# CN-Cape001.net
KiCad netlist of a schematic drawn in EAGLE
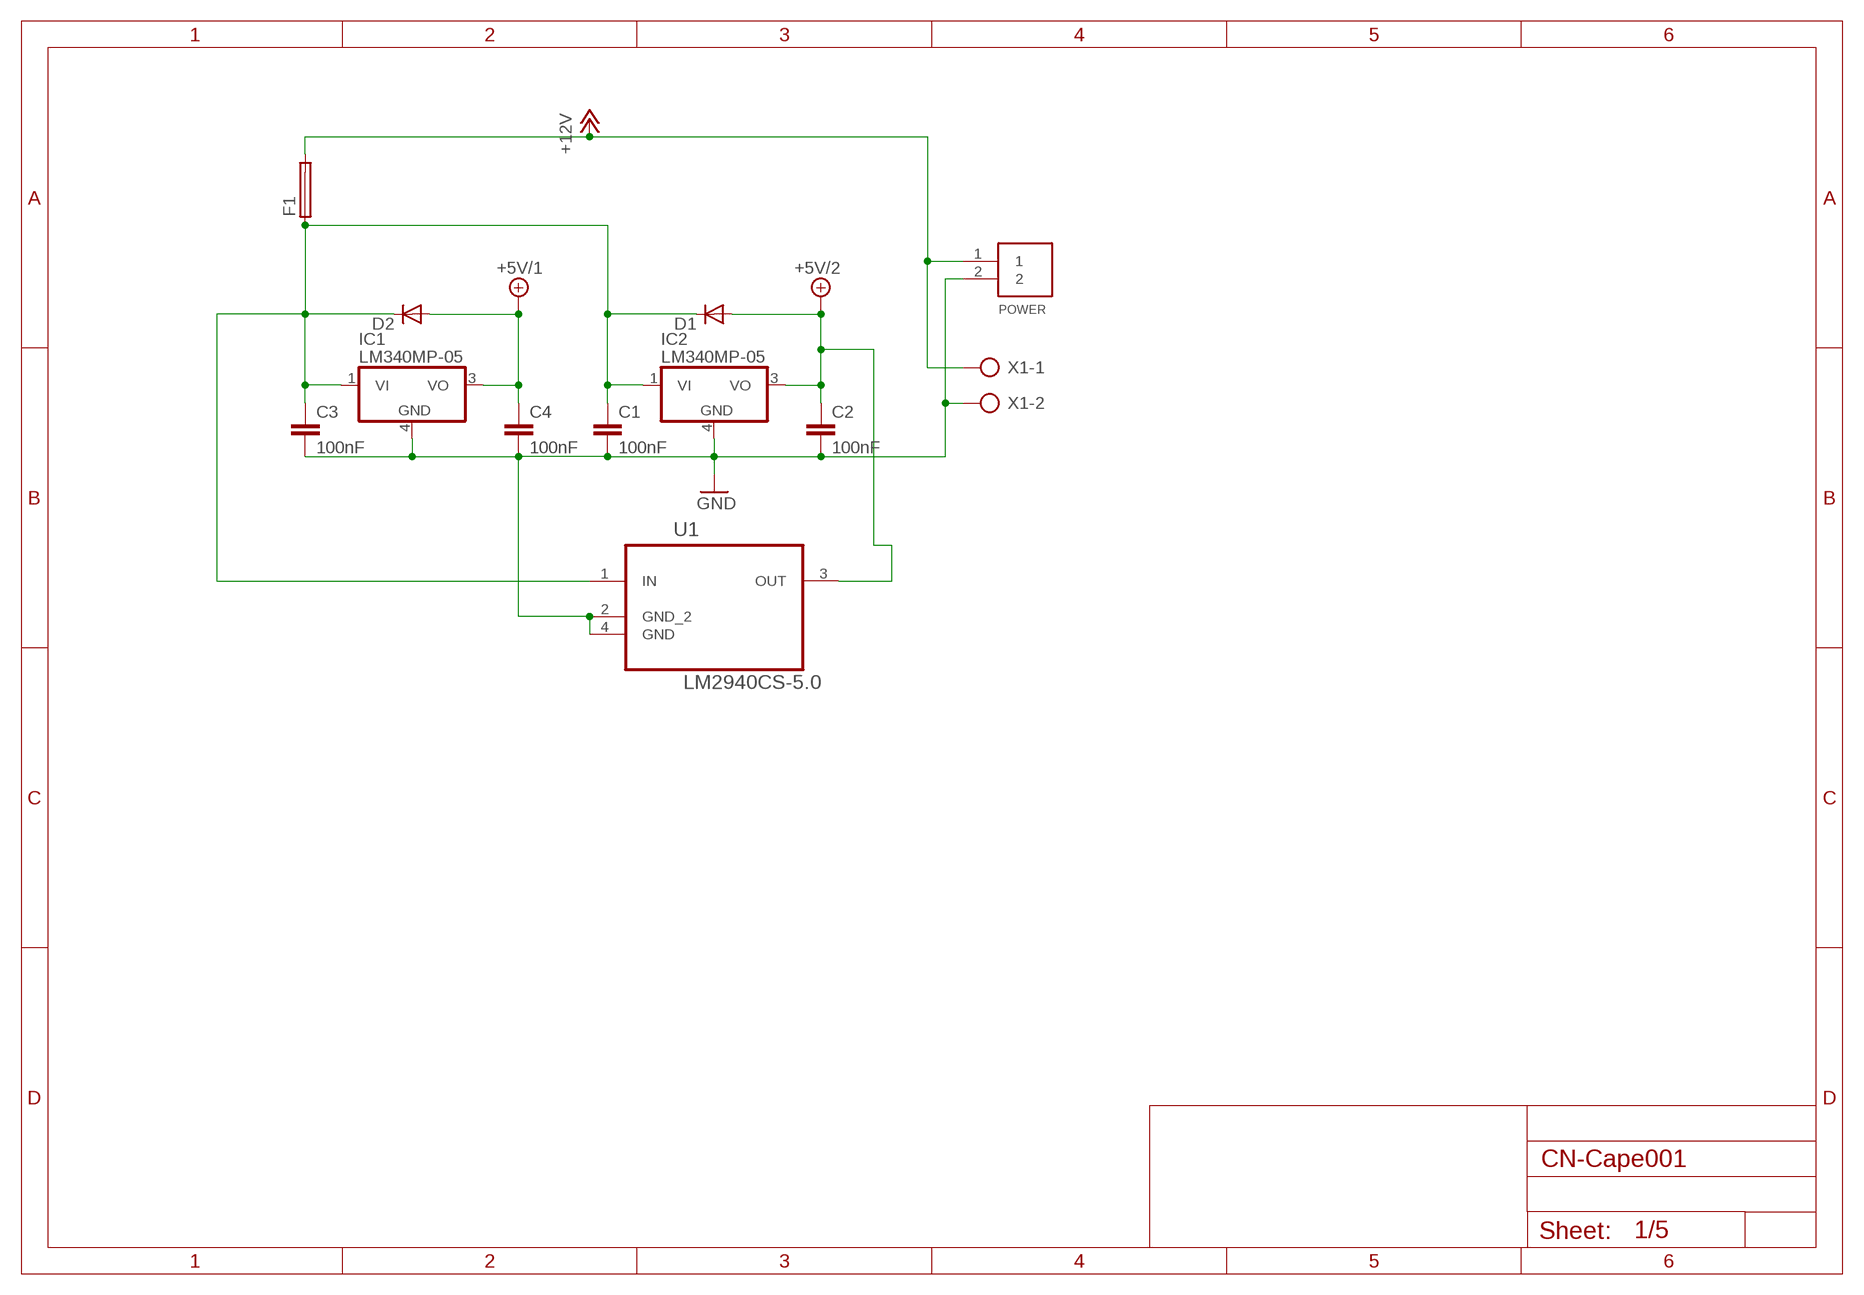
[diagram p0: schematic, sheet 1]
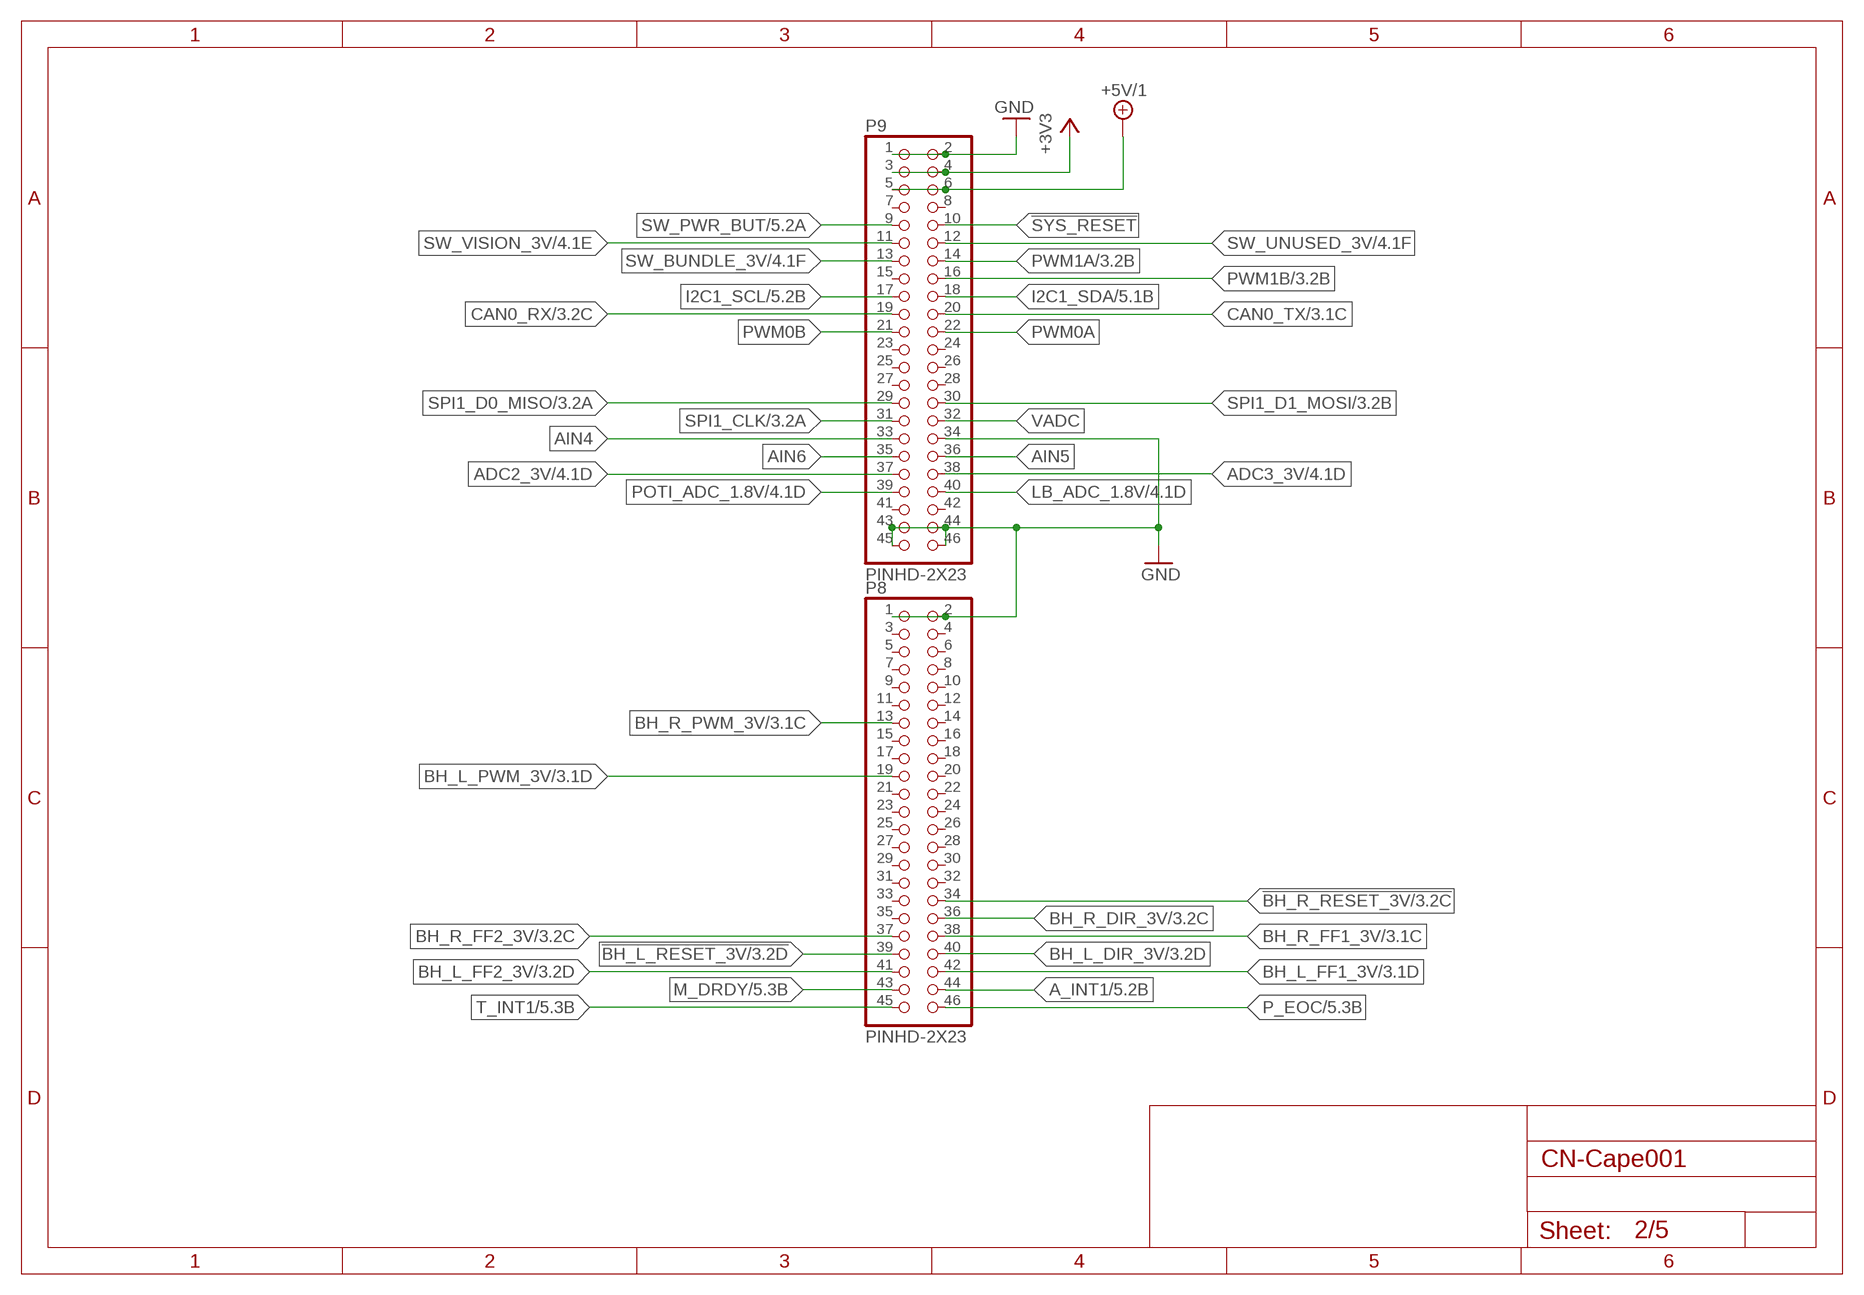
[diagram p1: schematic, sheet 2]
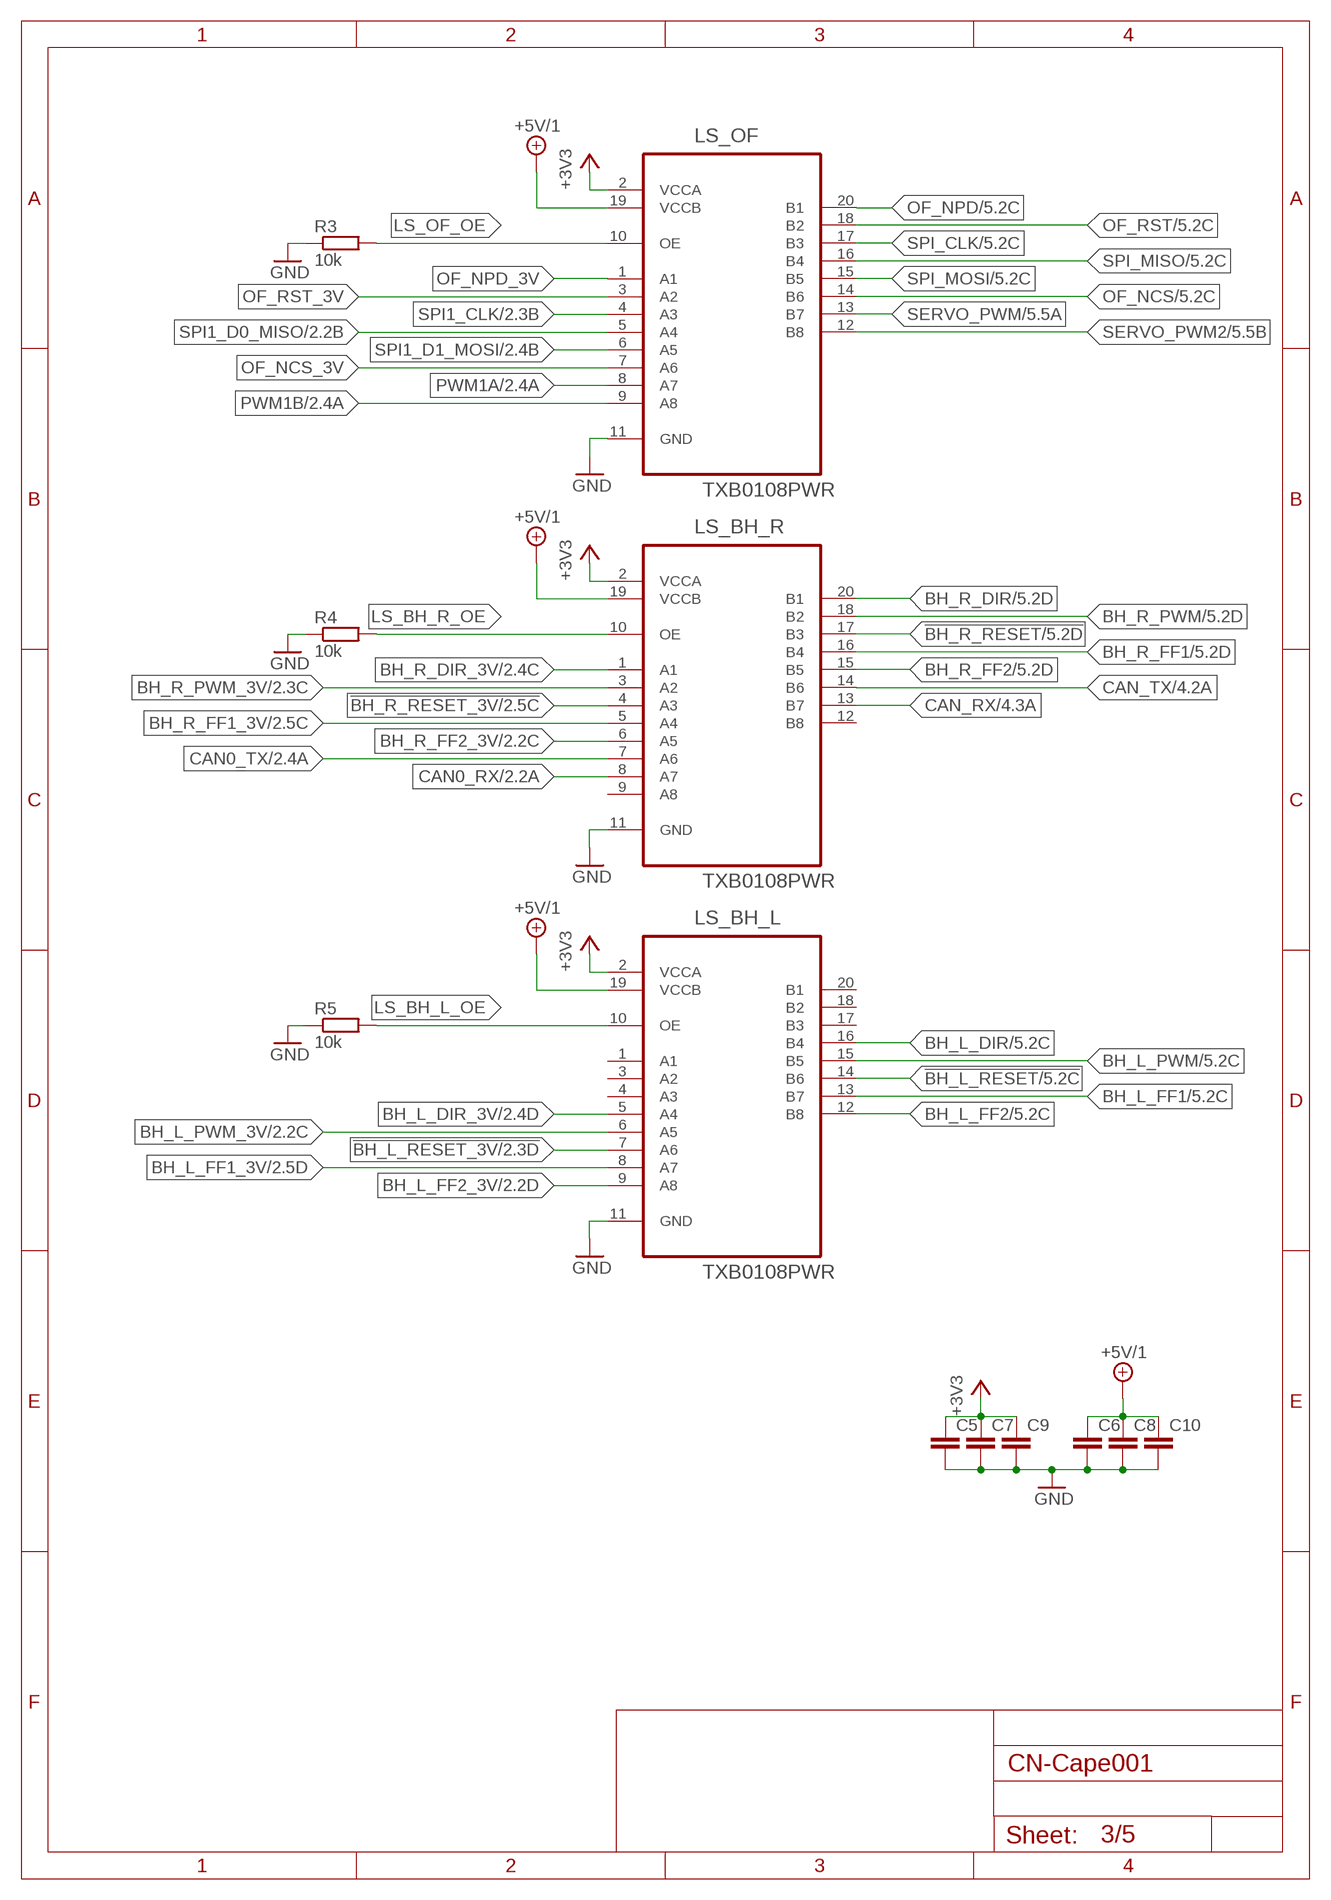
[diagram p2: schematic, sheet 3]
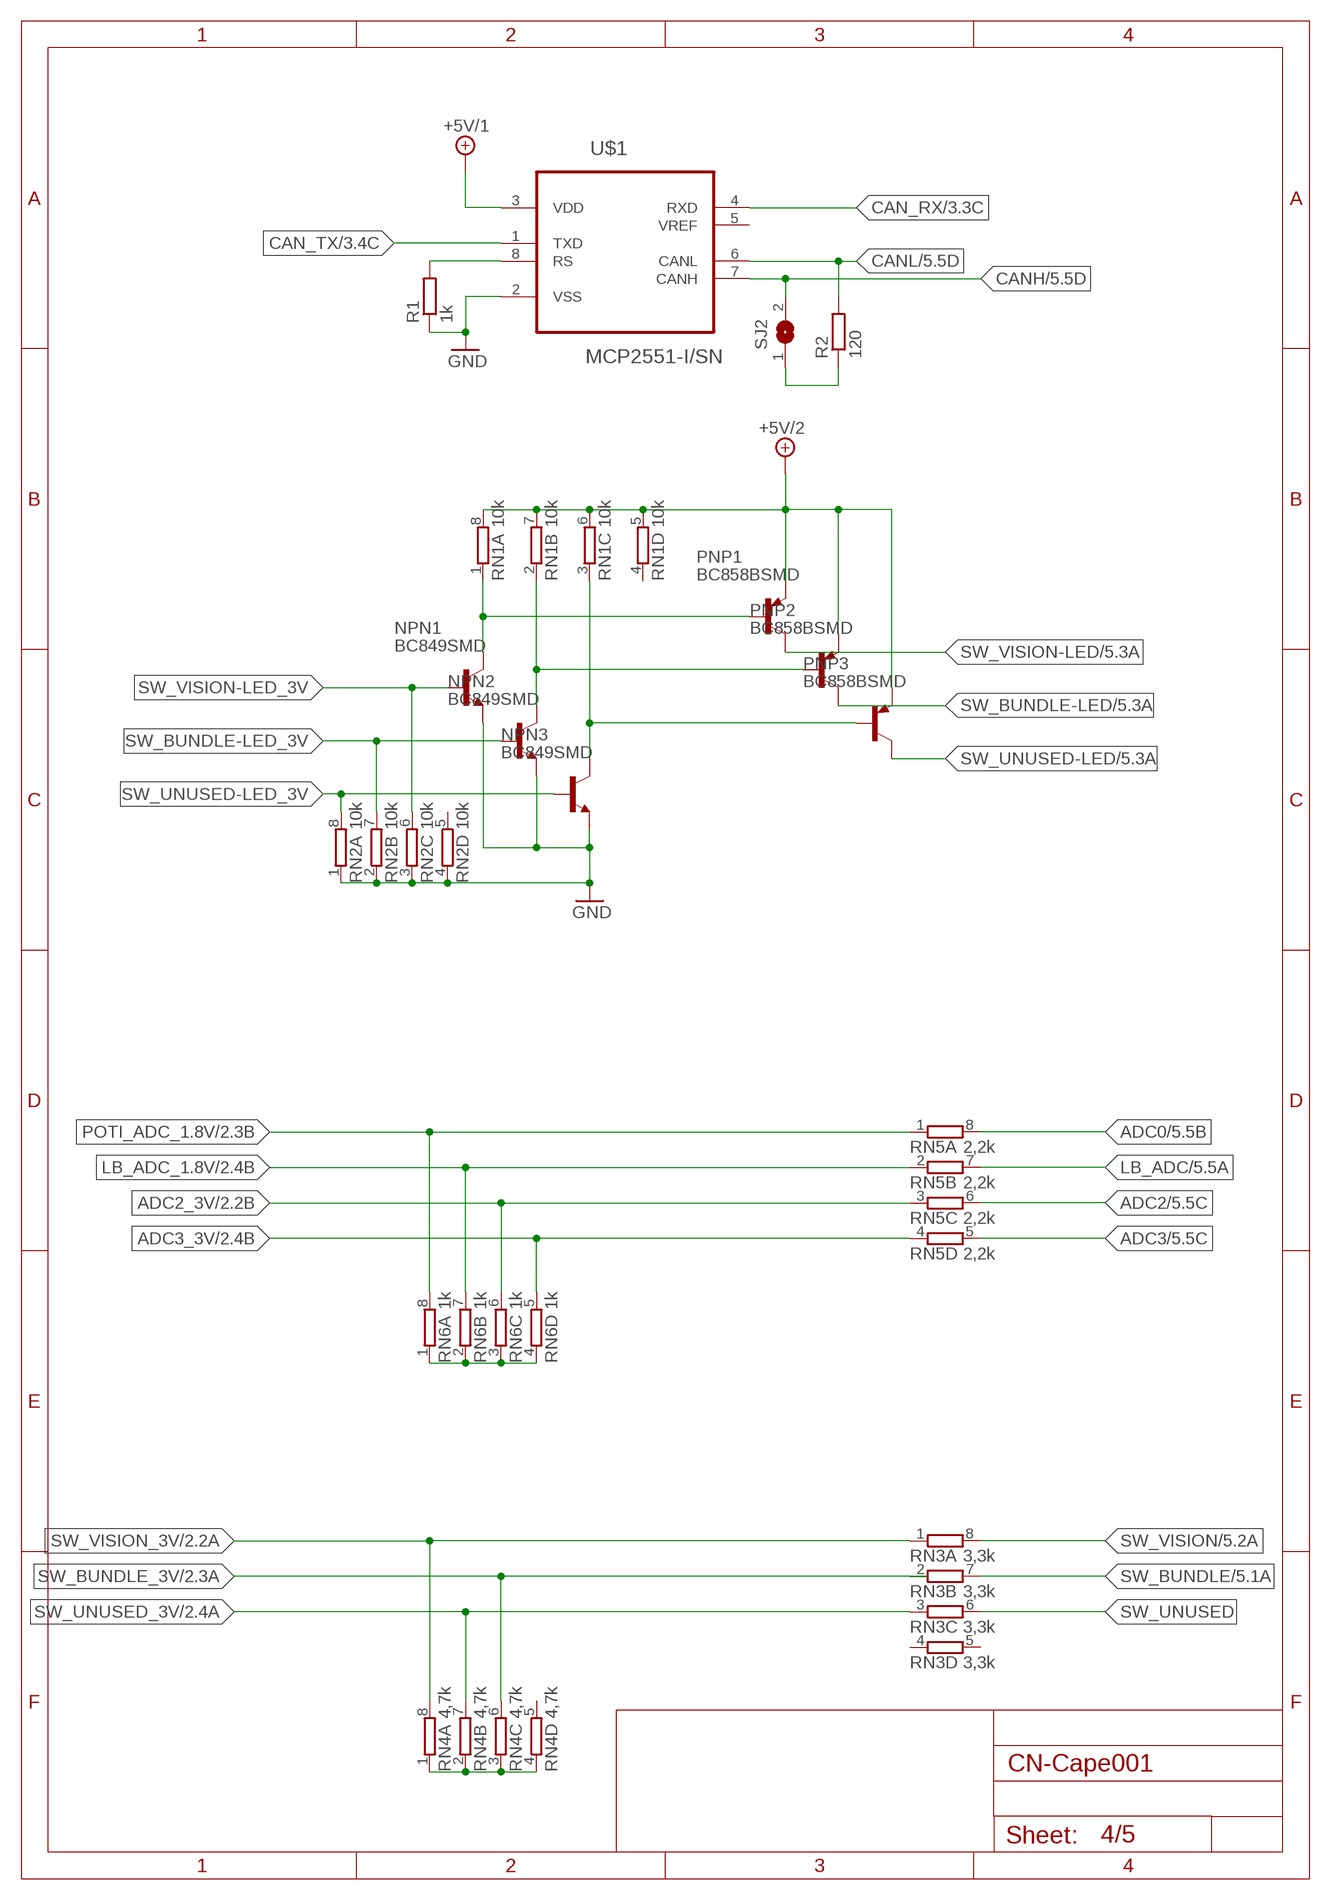
[diagram p3: schematic, sheet 4]
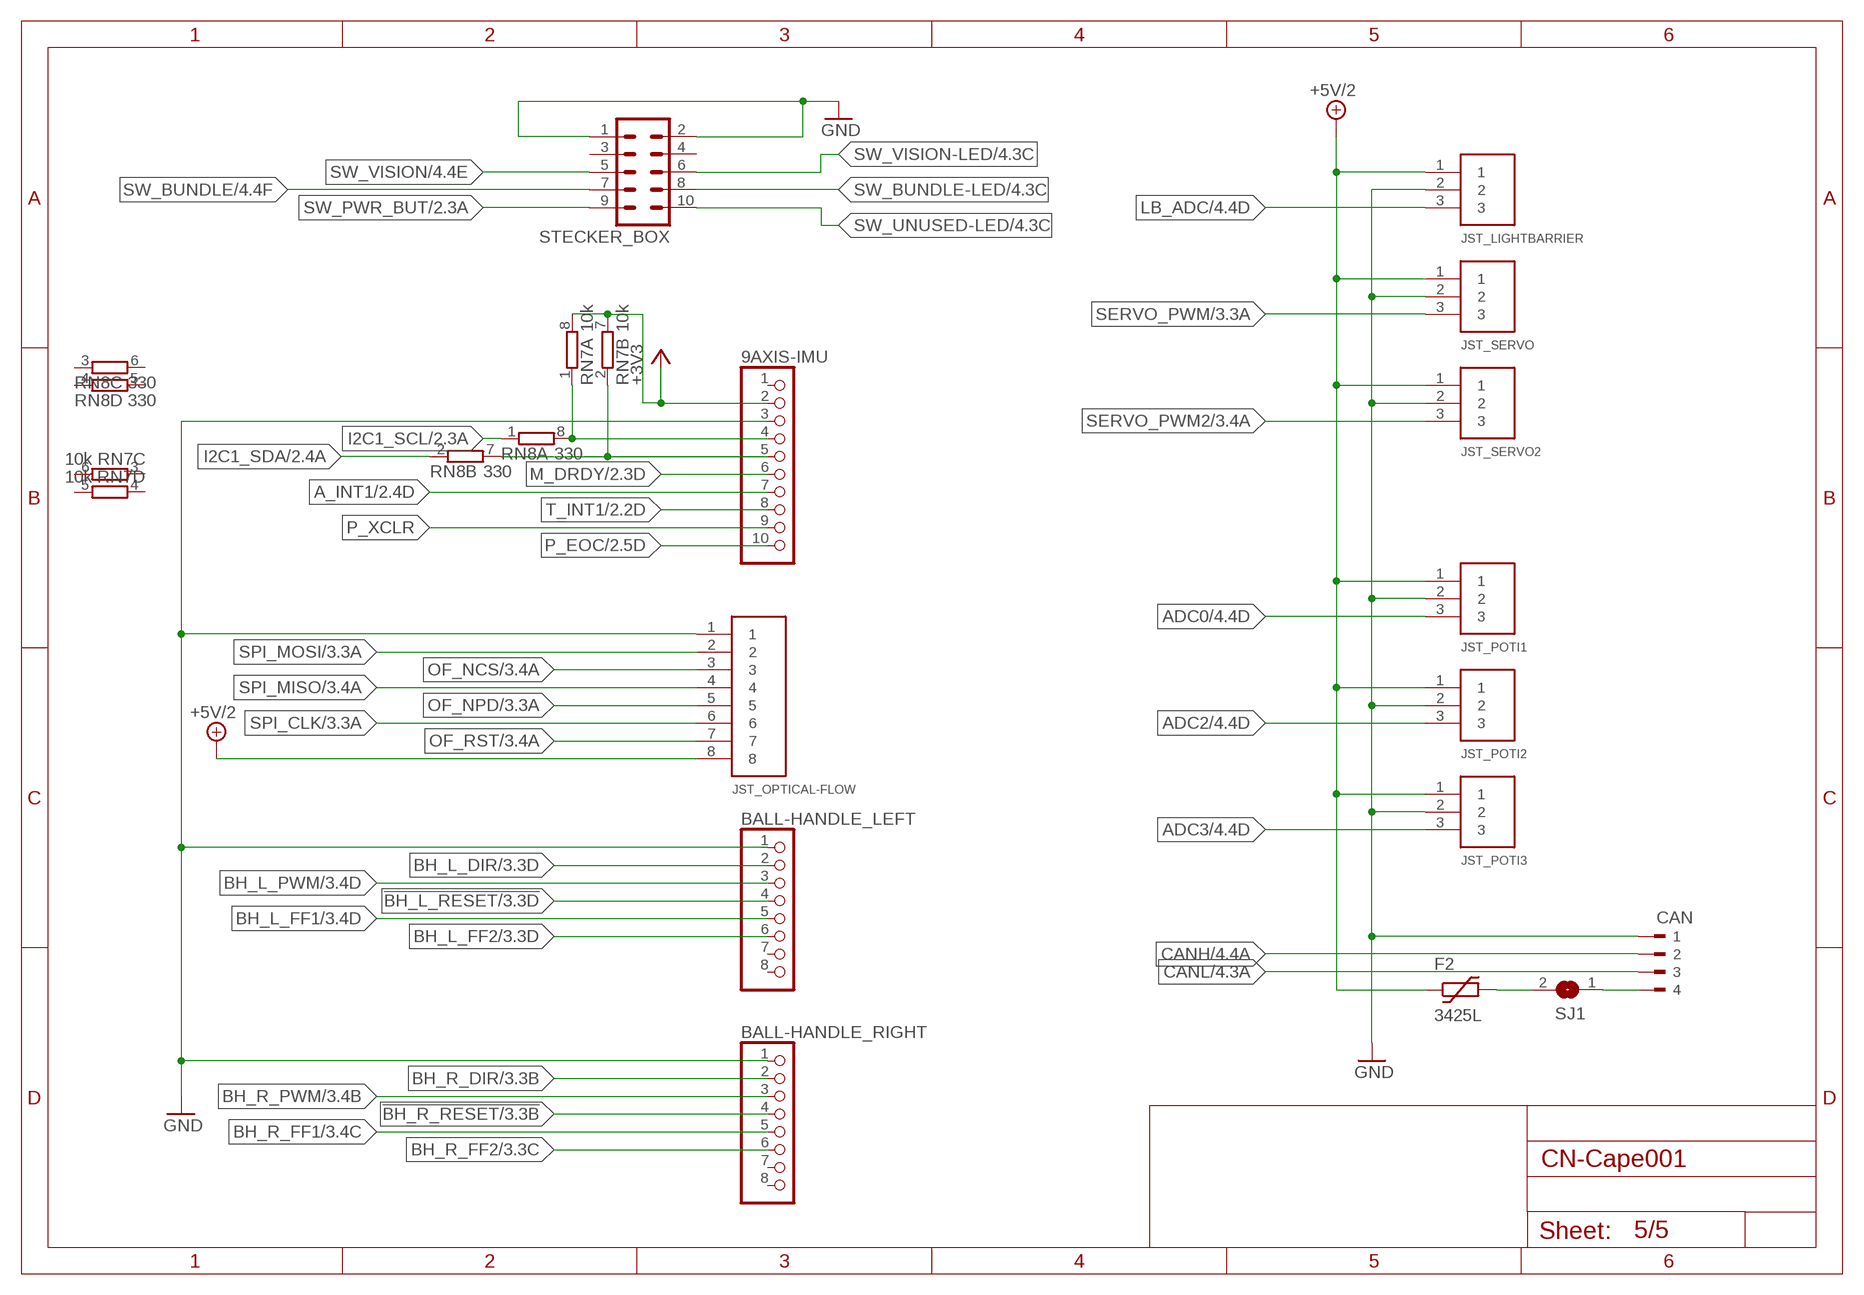
[diagram p4: schematic, sheet 5]

(export (version "E")
  (design (tool "Eeschema 10.0.6"))
  (components
    (comp (ref "C1")
      (value "100nF")
      (footprint "eagle-import:C0805")
      (libsource (lib "eagle-import") (part "C-EUC0805"))
    )
    (comp (ref "C2")
      (value "100nF")
      (footprint "eagle-import:C0805")
      (libsource (lib "eagle-import") (part "C-EUC0805"))
    )
    (comp (ref "C3")
      (value "100nF")
      (footprint "eagle-import:C0805")
      (libsource (lib "eagle-import") (part "C-EUC0805"))
    )
    (comp (ref "C4")
      (value "100nF")
      (footprint "eagle-import:C0805")
      (libsource (lib "eagle-import") (part "C-EUC0805"))
    )
    (comp (ref "D1")
      (value "DIODE-SOD123")
      (footprint "eagle-import:SOD123")
      (libsource (lib "eagle-import") (part "DIODE-SOD123"))
    )
    (comp (ref "D2")
      (value "DIODE-SOD123")
      (footprint "eagle-import:SOD123")
      (libsource (lib "eagle-import") (part "DIODE-SOD123"))
    )
    (comp (ref "F1")
      (value "SH22,5")
      (footprint "eagle-import:SH22,5")
      (libsource (lib "eagle-import") (part "SH22,5"))
    )
    (comp (ref "IC1")
      (value "LM340MP-05")
      (footprint "eagle-import:SOT223")
      (libsource (lib "eagle-import") (part "LM340?-MP05"))
    )
    (comp (ref "IC2")
      (value "LM340MP-05")
      (footprint "eagle-import:SOT223")
      (libsource (lib "eagle-import") (part "LM340?-MP05"))
    )
    (comp (ref "POWER")
      (value "S2PIN")
      (footprint "eagle-import:S2B-EH")
      (libsource (lib "eagle-import") (part "S2PIN"))
    )
    (comp (ref "U1")
      (value "LM2940CS-5.0")
      (footprint "eagle-import:TO254P1435X464-4N")
      (libsource (lib "eagle-import") (part "LM2940CS-5.0"))
    )
    (comp (ref "X1")
      (value "AK500/2-H")
      (footprint "eagle-import:AK500_2-H")
      (libsource (lib "eagle-import") (part "AK500/2-H"))
    )
    (comp (ref "C5")
      (value "C-EUC0805")
      (footprint "eagle-import:C0805")
      (libsource (lib "eagle-import") (part "C-EUC0805"))
    )
    (comp (ref "C6")
      (value "C-EUC0805")
      (footprint "eagle-import:C0805")
      (libsource (lib "eagle-import") (part "C-EUC0805"))
    )
    (comp (ref "C7")
      (value "C-EUC0805")
      (footprint "eagle-import:C0805")
      (libsource (lib "eagle-import") (part "C-EUC0805"))
    )
    (comp (ref "C8")
      (value "C-EUC0805")
      (footprint "eagle-import:C0805")
      (libsource (lib "eagle-import") (part "C-EUC0805"))
    )
    (comp (ref "C9")
      (value "C-EUC0805")
      (footprint "eagle-import:C0805")
      (libsource (lib "eagle-import") (part "C-EUC0805"))
    )
    (comp (ref "C10")
      (value "C-EUC0805")
      (footprint "eagle-import:C0805")
      (libsource (lib "eagle-import") (part "C-EUC0805"))
    )
    (comp (ref "LS_BH_L")
      (value "TXB0108PWR")
      (footprint "eagle-import:SOP65P640X120-20N")
      (libsource (lib "eagle-import") (part "TXB0108PWR"))
    )
    (comp (ref "LS_BH_R")
      (value "TXB0108PWR")
      (footprint "eagle-import:SOP65P640X120-20N")
      (libsource (lib "eagle-import") (part "TXB0108PWR"))
    )
    (comp (ref "LS_OF")
      (value "TXB0108PWR")
      (footprint "eagle-import:SOP65P640X120-20N")
      (libsource (lib "eagle-import") (part "TXB0108PWR"))
    )
    (comp (ref "R3")
      (value "10k")
      (footprint "eagle-import:R0603")
      (libsource (lib "eagle-import") (part "R-EU_R0603"))
    )
    (comp (ref "R4")
      (value "10k")
      (footprint "eagle-import:R0603")
      (libsource (lib "eagle-import") (part "R-EU_R0603"))
    )
    (comp (ref "R5")
      (value "10k")
      (footprint "eagle-import:R0603")
      (libsource (lib "eagle-import") (part "R-EU_R0603"))
    )
    (comp (ref "NPN1")
      (value "BC849SMD")
      (footprint "eagle-import:SOT23-BEC")
      (libsource (lib "eagle-import") (part "BC849SMD"))
    )
    (comp (ref "NPN2")
      (value "BC849SMD")
      (footprint "eagle-import:SOT23-BEC")
      (libsource (lib "eagle-import") (part "BC849SMD"))
    )
    (comp (ref "NPN3")
      (value "BC849SMD")
      (footprint "eagle-import:SOT23-BEC")
      (libsource (lib "eagle-import") (part "BC849SMD"))
    )
    (comp (ref "PNP1")
      (value "BC858BSMD")
      (footprint "eagle-import:SOT23-BEC")
      (libsource (lib "eagle-import") (part "BC858SMDB"))
    )
    (comp (ref "PNP2")
      (value "BC858BSMD")
      (footprint "eagle-import:SOT23-BEC")
      (libsource (lib "eagle-import") (part "BC858SMDB"))
    )
    (comp (ref "PNP3")
      (value "BC858BSMD")
      (footprint "eagle-import:SOT23-BEC")
      (libsource (lib "eagle-import") (part "BC858SMDB"))
    )
    (comp (ref "R1")
      (value "1k")
      (footprint "eagle-import:R0603")
      (libsource (lib "eagle-import") (part "R-EU_R0603"))
    )
    (comp (ref "R2")
      (value "120")
      (footprint "eagle-import:R0603")
      (libsource (lib "eagle-import") (part "R-EU_R0603"))
    )
    (comp (ref "RN1")
      (value "10k")
      (footprint "eagle-import:EXBV8V")
      (libsource (lib "eagle-import") (part "4R-NEXBV8V"))
    )
    (comp (ref "RN2")
      (value "10k")
      (footprint "eagle-import:EXBV8V")
      (libsource (lib "eagle-import") (part "4R-NEXBV8V"))
    )
    (comp (ref "RN3")
      (value "3,3k")
      (footprint "eagle-import:EXBV8V")
      (libsource (lib "eagle-import") (part "4R-NEXBV8V"))
    )
    (comp (ref "RN4")
      (value "4,7k")
      (footprint "eagle-import:EXBV8V")
      (libsource (lib "eagle-import") (part "4R-NEXBV8V"))
    )
    (comp (ref "RN5")
      (value "2,2k")
      (footprint "eagle-import:EXBV8V")
      (libsource (lib "eagle-import") (part "4R-NEXBV8V"))
    )
    (comp (ref "RN6")
      (value "1k")
      (footprint "eagle-import:EXBV8V")
      (libsource (lib "eagle-import") (part "4R-NEXBV8V"))
    )
    (comp (ref "SJ2") (value "SJ") (footprint "eagle-import:SJ") (libsource (lib "eagle-import") (part "SJ")))
    (comp (ref "U$1")
      (value "MCP2551-I/SN")
      (footprint "eagle-import:SOIC127P600X175-8N")
      (libsource (lib "eagle-import") (part "MCP2551-I/SN"))
    )
    (comp (ref "9AXIS-IMU")
      (value "PINHD-1X10")
      (footprint "eagle-import:1X10")
      (libsource (lib "eagle-import") (part "PINHD-1X10"))
    )
    (comp (ref "BALL-HANDLE_LEFT")
      (value "PINHD-1X8")
      (footprint "eagle-import:1X08")
      (libsource (lib "eagle-import") (part "PINHD-1X8"))
    )
    (comp (ref "BALL-HANDLE_RIGHT")
      (value "PINHD-1X8")
      (footprint "eagle-import:1X08")
      (libsource (lib "eagle-import") (part "PINHD-1X8"))
    )
    (comp (ref "CAN")
      (value "90-4")
      (footprint "eagle-import:90-4")
      (libsource (lib "eagle-import") (part "90-4"))
    )
    (comp (ref "F2")
      (value "3425L")
      (footprint "eagle-import:3425L")
      (libsource (lib "eagle-import") (part "3425L"))
    )
    (comp (ref "JST_LIGHTBARRIER")
      (value "S3PIN")
      (footprint "eagle-import:S3B-EH")
      (libsource (lib "eagle-import") (part "S3PIN"))
    )
    (comp (ref "JST_OPTICAL-FLOW")
      (value "S8PIN")
      (footprint "eagle-import:S8B-EH")
      (libsource (lib "eagle-import") (part "S8PIN"))
    )
    (comp (ref "JST_POTI1")
      (value "3PIN")
      (footprint "eagle-import:B3B-EH")
      (libsource (lib "eagle-import") (part "3PIN"))
    )
    (comp (ref "JST_POTI2")
      (value "3PIN")
      (footprint "eagle-import:B3B-EH")
      (libsource (lib "eagle-import") (part "3PIN"))
    )
    (comp (ref "JST_POTI3")
      (value "3PIN")
      (footprint "eagle-import:B3B-EH")
      (libsource (lib "eagle-import") (part "3PIN"))
    )
    (comp (ref "JST_SERVO")
      (value "S3PIN")
      (footprint "eagle-import:S3B-EH")
      (libsource (lib "eagle-import") (part "S3PIN"))
    )
    (comp (ref "JST_SERVO2")
      (value "3PIN")
      (footprint "eagle-import:B3B-EH")
      (libsource (lib "eagle-import") (part "3PIN"))
    )
    (comp (ref "RN7")
      (value "10k")
      (footprint "eagle-import:EXBV8V")
      (libsource (lib "eagle-import") (part "4R-NEXBV8V"))
    )
    (comp (ref "RN8")
      (value "330")
      (footprint "eagle-import:EXBV8V")
      (libsource (lib "eagle-import") (part "4R-NEXBV8V"))
    )
    (comp (ref "SJ1") (value "SJ") (footprint "eagle-import:SJ") (libsource (lib "eagle-import") (part "SJ")))
    (comp (ref "STECKER_BOX")
      (value "ML10")
      (footprint "eagle-import:ML10")
      (libsource (lib "eagle-import") (part "ML10"))
    )
    (comp (ref "P8")
      (value "PINHD-2X23")
      (footprint "eagle-import:2X23")
      (libsource (lib "eagle-import") (part "PINHD-2X23"))
    )
    (comp (ref "P9")
      (value "PINHD-2X23")
      (footprint "eagle-import:2X23")
      (libsource (lib "eagle-import") (part "PINHD-2X23"))
    )
  )
  (nets
    (net (code "1") (name "+3V3") (class "Default")
      (node (ref "9AXIS-IMU") (pin "2") (pinfunction "2_2") (pintype "passive"))
      (node (ref "C5") (pin "1") (pinfunction "1_1") (pintype "passive"))
      (node (ref "C7") (pin "1") (pinfunction "1_1") (pintype "passive"))
      (node (ref "C9") (pin "1") (pinfunction "1_1") (pintype "passive"))
      (node (ref "LS_BH_L") (pin "2") (pinfunction "VCCA_2") (pintype "power_in"))
      (node (ref "LS_BH_R") (pin "2") (pinfunction "VCCA_2") (pintype "power_in"))
      (node (ref "LS_OF") (pin "2") (pinfunction "VCCA_2") (pintype "power_in"))
      (node (ref "P9") (pin "3") (pinfunction "3_3") (pintype "passive"))
      (node (ref "P9") (pin "4") (pinfunction "4_4") (pintype "passive"))
      (node (ref "RN7") (pin "7") (pinfunction "2_7") (pintype "passive"))
      (node (ref "RN7") (pin "8") (pinfunction "2_8") (pintype "passive"))
    )
    (net (code "2") (name "+5V{slash}1") (class "Default")
      (node (ref "C10") (pin "1") (pinfunction "1_1") (pintype "passive"))
      (node (ref "C4") (pin "1") (pinfunction "1_1") (pintype "passive"))
      (node (ref "C6") (pin "1") (pinfunction "1_1") (pintype "passive"))
      (node (ref "C8") (pin "1") (pinfunction "1_1") (pintype "passive"))
      (node (ref "D2") (pin "A") (pinfunction "A_A") (pintype "passive"))
      (node (ref "IC1") (pin "3") (pinfunction "VO_3") (pintype "passive"))
      (node (ref "LS_BH_L") (pin "19") (pinfunction "VCCB_19") (pintype "power_in"))
      (node (ref "LS_BH_R") (pin "19") (pinfunction "VCCB_19") (pintype "power_in"))
      (node (ref "LS_OF") (pin "19") (pinfunction "VCCB_19") (pintype "power_in"))
      (node (ref "P9") (pin "5") (pinfunction "5_5") (pintype "passive"))
      (node (ref "P9") (pin "6") (pinfunction "6_6") (pintype "passive"))
      (node (ref "U$1") (pin "3") (pinfunction "VDD_3") (pintype "power_in"))
    )
    (net (code "3") (name "+5V{slash}2") (class "Default")
      (node (ref "C2") (pin "1") (pinfunction "1_1") (pintype "passive"))
      (node (ref "D1") (pin "A") (pinfunction "A_A") (pintype "passive"))
      (node (ref "F2") (pin "P$1") (pinfunction "1_P$1") (pintype "passive"))
      (node (ref "IC2") (pin "3") (pinfunction "VO_3") (pintype "passive"))
      (node (ref "JST_LIGHTBARRIER") (pin "1") (pinfunction "1_1") (pintype "bidirectional"))
      (node (ref "JST_OPTICAL-FLOW") (pin "8") (pinfunction "8_8") (pintype "bidirectional"))
      (node (ref "JST_POTI1") (pin "1") (pinfunction "1_1") (pintype "bidirectional"))
      (node (ref "JST_POTI2") (pin "1") (pinfunction "1_1") (pintype "bidirectional"))
      (node (ref "JST_POTI3") (pin "1") (pinfunction "1_1") (pintype "bidirectional"))
      (node (ref "JST_SERVO") (pin "1") (pinfunction "1_1") (pintype "bidirectional"))
      (node (ref "JST_SERVO2") (pin "1") (pinfunction "1_1") (pintype "bidirectional"))
      (node (ref "PNP1") (pin "E") (pinfunction "E_E") (pintype "passive"))
      (node (ref "PNP2") (pin "E") (pinfunction "E_E") (pintype "passive"))
      (node (ref "PNP3") (pin "E") (pinfunction "E_E") (pintype "passive"))
      (node (ref "RN1") (pin "5") (pinfunction "2_5") (pintype "passive"))
      (node (ref "RN1") (pin "6") (pinfunction "2_6") (pintype "passive"))
      (node (ref "RN1") (pin "7") (pinfunction "2_7") (pintype "passive"))
      (node (ref "RN1") (pin "8") (pinfunction "2_8") (pintype "passive"))
      (node (ref "U1") (pin "3") (pinfunction "OUT_3") (pintype "output"))
    )
    (net (code "4") (name "+12V") (class "Default")
      (node (ref "F1") (pin "2") (pinfunction "2_2") (pintype "passive"))
      (node (ref "POWER") (pin "1") (pinfunction "1_1") (pintype "bidirectional"))
      (node (ref "X1") (pin "1") (pinfunction "KL_1") (pintype "passive"))
    )
    (net (code "5") (name "ADC0") (class "Default")
      (node (ref "JST_POTI1") (pin "3") (pinfunction "3_3") (pintype "bidirectional"))
      (node (ref "RN5") (pin "8") (pinfunction "2_8") (pintype "passive"))
    )
    (net (code "6") (name "ADC2") (class "Default")
      (node (ref "JST_POTI2") (pin "3") (pinfunction "3_3") (pintype "bidirectional"))
      (node (ref "RN5") (pin "6") (pinfunction "2_6") (pintype "passive"))
    )
    (net (code "7") (name "ADC2_3V") (class "Default")
      (node (ref "P9") (pin "37") (pinfunction "37_37") (pintype "passive"))
      (node (ref "RN5") (pin "3") (pinfunction "1_3") (pintype "passive"))
      (node (ref "RN6") (pin "6") (pinfunction "2_6") (pintype "passive"))
    )
    (net (code "8") (name "ADC3") (class "Default")
      (node (ref "JST_POTI3") (pin "3") (pinfunction "3_3") (pintype "bidirectional"))
      (node (ref "RN5") (pin "5") (pinfunction "2_5") (pintype "passive"))
    )
    (net (code "9") (name "ADC3_3V") (class "Default")
      (node (ref "P9") (pin "38") (pinfunction "38_38") (pintype "passive"))
      (node (ref "RN5") (pin "4") (pinfunction "1_4") (pintype "passive"))
      (node (ref "RN6") (pin "5") (pinfunction "2_5") (pintype "passive"))
    )
    (net (code "10") (name "AIN4") (class "Default")
      (node (ref "P9") (pin "33") (pinfunction "33_33") (pintype "passive"))
    )
    (net (code "11") (name "AIN5") (class "Default")
      (node (ref "P9") (pin "36") (pinfunction "36_36") (pintype "passive"))
    )
    (net (code "12") (name "AIN6") (class "Default")
      (node (ref "P9") (pin "35") (pinfunction "35_35") (pintype "passive"))
    )
    (net (code "13") (name "A_INT1") (class "Default")
      (node (ref "9AXIS-IMU") (pin "7") (pinfunction "7_7") (pintype "passive"))
      (node (ref "P8") (pin "44") (pinfunction "44_44") (pintype "passive"))
    )
    (net (code "14") (name "BH_L_DIR") (class "Default")
      (node (ref "BALL-HANDLE_LEFT") (pin "2") (pinfunction "2_2") (pintype "passive"))
      (node (ref "LS_BH_L") (pin "16") (pinfunction "B4_16") (pintype "bidirectional"))
    )
    (net (code "15") (name "BH_L_DIR_3V") (class "Default")
      (node (ref "LS_BH_L") (pin "5") (pinfunction "A4_5") (pintype "bidirectional"))
      (node (ref "P8") (pin "40") (pinfunction "40_40") (pintype "passive"))
    )
    (net (code "16") (name "BH_L_FF1") (class "Default")
      (node (ref "BALL-HANDLE_LEFT") (pin "5") (pinfunction "5_5") (pintype "passive"))
      (node (ref "LS_BH_L") (pin "13") (pinfunction "B7_13") (pintype "bidirectional"))
    )
    (net (code "17") (name "BH_L_FF1_3V") (class "Default")
      (node (ref "LS_BH_L") (pin "8") (pinfunction "A7_8") (pintype "bidirectional"))
      (node (ref "P8") (pin "42") (pinfunction "42_42") (pintype "passive"))
    )
    (net (code "18") (name "BH_L_FF2") (class "Default")
      (node (ref "BALL-HANDLE_LEFT") (pin "6") (pinfunction "6_6") (pintype "passive"))
      (node (ref "LS_BH_L") (pin "12") (pinfunction "B8_12") (pintype "bidirectional"))
    )
    (net (code "19") (name "BH_L_FF2_3V") (class "Default")
      (node (ref "LS_BH_L") (pin "9") (pinfunction "A8_9") (pintype "bidirectional"))
      (node (ref "P8") (pin "41") (pinfunction "41_41") (pintype "passive"))
    )
    (net (code "20") (name "BH_L_PWM") (class "Default")
      (node (ref "BALL-HANDLE_LEFT") (pin "3") (pinfunction "3_3") (pintype "passive"))
      (node (ref "LS_BH_L") (pin "15") (pinfunction "B5_15") (pintype "bidirectional"))
    )
    (net (code "21") (name "BH_L_PWM_3V") (class "Default")
      (node (ref "LS_BH_L") (pin "6") (pinfunction "A5_6") (pintype "bidirectional"))
      (node (ref "P8") (pin "19") (pinfunction "19_19") (pintype "passive"))
    )
    (net (code "22") (name "BH_R_DIR") (class "Default")
      (node (ref "BALL-HANDLE_RIGHT") (pin "2") (pinfunction "2_2") (pintype "passive"))
      (node (ref "LS_BH_R") (pin "20") (pinfunction "B1_20") (pintype "bidirectional"))
    )
    (net (code "23") (name "BH_R_DIR_3V") (class "Default")
      (node (ref "LS_BH_R") (pin "1") (pinfunction "A1_1") (pintype "bidirectional"))
      (node (ref "P8") (pin "36") (pinfunction "36_36") (pintype "passive"))
    )
    (net (code "24") (name "BH_R_FF1") (class "Default")
      (node (ref "BALL-HANDLE_RIGHT") (pin "5") (pinfunction "5_5") (pintype "passive"))
      (node (ref "LS_BH_R") (pin "16") (pinfunction "B4_16") (pintype "bidirectional"))
    )
    (net (code "25") (name "BH_R_FF1_3V") (class "Default")
      (node (ref "LS_BH_R") (pin "5") (pinfunction "A4_5") (pintype "bidirectional"))
      (node (ref "P8") (pin "38") (pinfunction "38_38") (pintype "passive"))
    )
    (net (code "26") (name "BH_R_FF2") (class "Default")
      (node (ref "BALL-HANDLE_RIGHT") (pin "6") (pinfunction "6_6") (pintype "passive"))
      (node (ref "LS_BH_R") (pin "15") (pinfunction "B5_15") (pintype "bidirectional"))
    )
    (net (code "27") (name "BH_R_FF2_3V") (class "Default")
      (node (ref "LS_BH_R") (pin "6") (pinfunction "A5_6") (pintype "bidirectional"))
      (node (ref "P8") (pin "37") (pinfunction "37_37") (pintype "passive"))
    )
    (net (code "28") (name "BH_R_PWM") (class "Default")
      (node (ref "BALL-HANDLE_RIGHT") (pin "3") (pinfunction "3_3") (pintype "passive"))
      (node (ref "LS_BH_R") (pin "18") (pinfunction "B2_18") (pintype "bidirectional"))
    )
    (net (code "29") (name "BH_R_PWM_3V") (class "Default")
      (node (ref "LS_BH_R") (pin "3") (pinfunction "A2_3") (pintype "bidirectional"))
      (node (ref "P8") (pin "13") (pinfunction "13_13") (pintype "passive"))
    )
    (net (code "30") (name "CAN0_RX") (class "Default")
      (node (ref "LS_BH_R") (pin "8") (pinfunction "A7_8") (pintype "bidirectional"))
      (node (ref "P9") (pin "19") (pinfunction "19_19") (pintype "passive"))
    )
    (net (code "31") (name "CAN0_TX") (class "Default")
      (node (ref "LS_BH_R") (pin "7") (pinfunction "A6_7") (pintype "bidirectional"))
      (node (ref "P9") (pin "20") (pinfunction "20_20") (pintype "passive"))
    )
    (net (code "32") (name "CANH") (class "Default")
      (node (ref "CAN") (pin "2") (pinfunction "2_2") (pintype "passive"))
      (node (ref "SJ2") (pin "2") (pinfunction "2_2") (pintype "passive"))
      (node (ref "U$1") (pin "7") (pinfunction "CANH_7") (pintype "bidirectional"))
    )
    (net (code "33") (name "CANL") (class "Default")
      (node (ref "CAN") (pin "3") (pinfunction "3_3") (pintype "passive"))
      (node (ref "R2") (pin "2") (pinfunction "2_2") (pintype "passive"))
      (node (ref "U$1") (pin "6") (pinfunction "CANL_6") (pintype "bidirectional"))
    )
    (net (code "34") (name "CAN_RX") (class "Default")
      (node (ref "LS_BH_R") (pin "13") (pinfunction "B7_13") (pintype "bidirectional"))
      (node (ref "U$1") (pin "4") (pinfunction "RXD_4") (pintype "output"))
    )
    (net (code "35") (name "CAN_TX") (class "Default")
      (node (ref "LS_BH_R") (pin "14") (pinfunction "B6_14") (pintype "bidirectional"))
      (node (ref "U$1") (pin "1") (pinfunction "TXD_1") (pintype "input"))
    )
    (net (code "36") (name "GND") (class "Default")
      (node (ref "9AXIS-IMU") (pin "3") (pinfunction "3_3") (pintype "passive"))
      (node (ref "BALL-HANDLE_LEFT") (pin "1") (pinfunction "1_1") (pintype "passive"))
      (node (ref "BALL-HANDLE_RIGHT") (pin "1") (pinfunction "1_1") (pintype "passive"))
      (node (ref "C1") (pin "2") (pinfunction "2_2") (pintype "passive"))
      (node (ref "C10") (pin "2") (pinfunction "2_2") (pintype "passive"))
      (node (ref "C2") (pin "2") (pinfunction "2_2") (pintype "passive"))
      (node (ref "C3") (pin "2") (pinfunction "2_2") (pintype "passive"))
      (node (ref "C4") (pin "2") (pinfunction "2_2") (pintype "passive"))
      (node (ref "C5") (pin "2") (pinfunction "2_2") (pintype "passive"))
      (node (ref "C6") (pin "2") (pinfunction "2_2") (pintype "passive"))
      (node (ref "C7") (pin "2") (pinfunction "2_2") (pintype "passive"))
      (node (ref "C8") (pin "2") (pinfunction "2_2") (pintype "passive"))
      (node (ref "C9") (pin "2") (pinfunction "2_2") (pintype "passive"))
      (node (ref "CAN") (pin "1") (pinfunction "1_1") (pintype "passive"))
      (node (ref "IC1") (pin "4") (pinfunction "GND_4") (pintype "passive"))
      (node (ref "IC2") (pin "4") (pinfunction "GND_4") (pintype "passive"))
      (node (ref "JST_LIGHTBARRIER") (pin "2") (pinfunction "2_2") (pintype "bidirectional"))
      (node (ref "JST_OPTICAL-FLOW") (pin "1") (pinfunction "1_1") (pintype "bidirectional"))
      (node (ref "JST_POTI1") (pin "2") (pinfunction "2_2") (pintype "bidirectional"))
      (node (ref "JST_POTI2") (pin "2") (pinfunction "2_2") (pintype "bidirectional"))
      (node (ref "JST_POTI3") (pin "2") (pinfunction "2_2") (pintype "bidirectional"))
      (node (ref "JST_SERVO") (pin "2") (pinfunction "2_2") (pintype "bidirectional"))
      (node (ref "JST_SERVO2") (pin "2") (pinfunction "2_2") (pintype "bidirectional"))
      (node (ref "LS_BH_L") (pin "11") (pinfunction "GND_11") (pintype "passive"))
      (node (ref "LS_BH_R") (pin "11") (pinfunction "GND_11") (pintype "passive"))
      (node (ref "LS_OF") (pin "11") (pinfunction "GND_11") (pintype "passive"))
      (node (ref "NPN1") (pin "E") (pinfunction "E_E") (pintype "passive"))
      (node (ref "NPN2") (pin "E") (pinfunction "E_E") (pintype "passive"))
      (node (ref "NPN3") (pin "E") (pinfunction "E_E") (pintype "passive"))
      (node (ref "P8") (pin "1") (pinfunction "1_1") (pintype "passive"))
      (node (ref "P8") (pin "2") (pinfunction "2_2") (pintype "passive"))
      (node (ref "P9") (pin "1") (pinfunction "1_1") (pintype "passive"))
      (node (ref "P9") (pin "2") (pinfunction "2_2") (pintype "passive"))
      (node (ref "P9") (pin "34") (pinfunction "34_34") (pintype "passive"))
      (node (ref "P9") (pin "43") (pinfunction "43_43") (pintype "passive"))
      (node (ref "P9") (pin "44") (pinfunction "44_44") (pintype "passive"))
      (node (ref "P9") (pin "45") (pinfunction "45_45") (pintype "passive"))
      (node (ref "P9") (pin "46") (pinfunction "46_46") (pintype "passive"))
      (node (ref "POWER") (pin "2") (pinfunction "2_2") (pintype "bidirectional"))
      (node (ref "R1") (pin "1") (pinfunction "1_1") (pintype "passive"))
      (node (ref "R3") (pin "1") (pinfunction "1_1") (pintype "passive"))
      (node (ref "R4") (pin "1") (pinfunction "1_1") (pintype "passive"))
      (node (ref "R5") (pin "1") (pinfunction "1_1") (pintype "passive"))
      (node (ref "RN2") (pin "1") (pinfunction "1_1") (pintype "passive"))
      (node (ref "RN2") (pin "2") (pinfunction "1_2") (pintype "passive"))
      (node (ref "RN2") (pin "3") (pinfunction "1_3") (pintype "passive"))
      (node (ref "RN2") (pin "4") (pinfunction "1_4") (pintype "passive"))
      (node (ref "STECKER_BOX") (pin "1") (pinfunction "1_1") (pintype "passive"))
      (node (ref "STECKER_BOX") (pin "2") (pinfunction "2_2") (pintype "passive"))
      (node (ref "U$1") (pin "2") (pinfunction "VSS_2") (pintype "passive"))
      (node (ref "U1") (pin "2") (pinfunction "GND_2_2") (pintype "passive"))
      (node (ref "U1") (pin "4") (pinfunction "GND_4") (pintype "passive"))
      (node (ref "X1") (pin "2") (pinfunction "KL_2") (pintype "passive"))
    )
    (net (code "37") (name "I2C1_SCL") (class "Default")
      (node (ref "P9") (pin "17") (pinfunction "17_17") (pintype "passive"))
      (node (ref "RN8") (pin "1") (pinfunction "1_1") (pintype "passive"))
    )
    (net (code "38") (name "I2C1_SDA") (class "Default")
      (node (ref "P9") (pin "18") (pinfunction "18_18") (pintype "passive"))
      (node (ref "RN8") (pin "2") (pinfunction "1_2") (pintype "passive"))
    )
    (net (code "39") (name "LB_ADC") (class "Default")
      (node (ref "JST_LIGHTBARRIER") (pin "3") (pinfunction "3_3") (pintype "bidirectional"))
      (node (ref "RN5") (pin "7") (pinfunction "2_7") (pintype "passive"))
    )
    (net (code "40") (name "LB_ADC_1.8V") (class "Default")
      (node (ref "P9") (pin "40") (pinfunction "40_40") (pintype "passive"))
      (node (ref "RN5") (pin "2") (pinfunction "1_2") (pintype "passive"))
      (node (ref "RN6") (pin "7") (pinfunction "2_7") (pintype "passive"))
    )
    (net (code "41") (name "LS_BH_L_OE") (class "Default")
      (node (ref "LS_BH_L") (pin "10") (pinfunction "OE_10") (pintype "input"))
      (node (ref "R5") (pin "2") (pinfunction "2_2") (pintype "passive"))
    )
    (net (code "42") (name "LS_BH_R_OE") (class "Default")
      (node (ref "LS_BH_R") (pin "10") (pinfunction "OE_10") (pintype "input"))
      (node (ref "R4") (pin "2") (pinfunction "2_2") (pintype "passive"))
    )
    (net (code "43") (name "LS_OF_OE") (class "Default")
      (node (ref "LS_OF") (pin "10") (pinfunction "OE_10") (pintype "input"))
      (node (ref "R3") (pin "2") (pinfunction "2_2") (pintype "passive"))
    )
    (net (code "44") (name "M_DRDY") (class "Default")
      (node (ref "9AXIS-IMU") (pin "6") (pinfunction "6_6") (pintype "passive"))
      (node (ref "P8") (pin "43") (pinfunction "43_43") (pintype "passive"))
    )
    (net (code "45") (name "Net-(CAN-Pad4)") (class "Default")
      (node (ref "CAN") (pin "4") (pinfunction "4_4") (pintype "passive"))
      (node (ref "SJ1") (pin "1") (pinfunction "1_1") (pintype "passive"))
    )
    (net (code "46") (name "Net-(F2-2)") (class "Default")
      (node (ref "F2") (pin "P$2") (pinfunction "2_P$2") (pintype "passive"))
      (node (ref "SJ1") (pin "2") (pinfunction "2_2") (pintype "passive"))
    )
    (net (code "47") (name "Net-(IC1-VI)") (class "Default")
      (node (ref "C1") (pin "1") (pinfunction "1_1") (pintype "passive"))
      (node (ref "C3") (pin "1") (pinfunction "1_1") (pintype "passive"))
      (node (ref "D1") (pin "C") (pinfunction "C_C") (pintype "passive"))
      (node (ref "D2") (pin "C") (pinfunction "C_C") (pintype "passive"))
      (node (ref "F1") (pin "1") (pinfunction "1_1") (pintype "passive"))
      (node (ref "IC1") (pin "1") (pinfunction "VI_1") (pintype "input"))
      (node (ref "IC2") (pin "1") (pinfunction "VI_1") (pintype "input"))
      (node (ref "U1") (pin "1") (pinfunction "IN_1") (pintype "input"))
    )
    (net (code "48") (name "Net-(NPN1-PadC)") (class "Default")
      (node (ref "NPN1") (pin "C") (pinfunction "C_C") (pintype "passive"))
      (node (ref "PNP1") (pin "B") (pinfunction "B_B") (pintype "passive"))
      (node (ref "RN1") (pin "1") (pinfunction "1_1") (pintype "passive"))
    )
    (net (code "49") (name "Net-(R2-Pad1)") (class "Default")
      (node (ref "R2") (pin "1") (pinfunction "1_1") (pintype "passive"))
      (node (ref "SJ2") (pin "1") (pinfunction "1_1") (pintype "passive"))
    )
    (net (code "50") (name "Net-(RN1B-1)") (class "Default")
      (node (ref "NPN2") (pin "C") (pinfunction "C_C") (pintype "passive"))
      (node (ref "PNP2") (pin "B") (pinfunction "B_B") (pintype "passive"))
      (node (ref "RN1") (pin "2") (pinfunction "1_2") (pintype "passive"))
    )
    (net (code "51") (name "Net-(RN1C-1)") (class "Default")
      (node (ref "NPN3") (pin "C") (pinfunction "C_C") (pintype "passive"))
      (node (ref "PNP3") (pin "B") (pinfunction "B_B") (pintype "passive"))
      (node (ref "RN1") (pin "3") (pinfunction "1_3") (pintype "passive"))
    )
    (net (code "52") (name "Net-(RN4B-1)") (class "Default")
      (node (ref "RN4") (pin "1") (pinfunction "1_1") (pintype "passive"))
      (node (ref "RN4") (pin "2") (pinfunction "1_2") (pintype "passive"))
      (node (ref "RN4") (pin "3") (pinfunction "1_3") (pintype "passive"))
      (node (ref "RN4") (pin "4") (pinfunction "1_4") (pintype "passive"))
    )
    (net (code "53") (name "Net-(RN6B-1)") (class "Default")
      (node (ref "RN6") (pin "1") (pinfunction "1_1") (pintype "passive"))
      (node (ref "RN6") (pin "2") (pinfunction "1_2") (pintype "passive"))
      (node (ref "RN6") (pin "3") (pinfunction "1_3") (pintype "passive"))
      (node (ref "RN6") (pin "4") (pinfunction "1_4") (pintype "passive"))
    )
    (net (code "54") (name "Net-(RN7B-1)") (class "Default")
      (node (ref "9AXIS-IMU") (pin "5") (pinfunction "5_5") (pintype "passive"))
      (node (ref "RN7") (pin "2") (pinfunction "1_2") (pintype "passive"))
      (node (ref "RN8") (pin "7") (pinfunction "2_7") (pintype "passive"))
    )
    (net (code "55") (name "Net-(RN8A-2)") (class "Default")
      (node (ref "9AXIS-IMU") (pin "4") (pinfunction "4_4") (pintype "passive"))
      (node (ref "RN7") (pin "1") (pinfunction "1_1") (pintype "passive"))
      (node (ref "RN8") (pin "8") (pinfunction "2_8") (pintype "passive"))
    )
    (net (code "56") (name "Net-(U$1-RS)") (class "Default")
      (node (ref "R1") (pin "2") (pinfunction "2_2") (pintype "passive"))
      (node (ref "U$1") (pin "8") (pinfunction "RS_8") (pintype "input"))
    )
    (net (code "57") (name "OF_NCS") (class "Default")
      (node (ref "JST_OPTICAL-FLOW") (pin "3") (pinfunction "3_3") (pintype "bidirectional"))
      (node (ref "LS_OF") (pin "14") (pinfunction "B6_14") (pintype "bidirectional"))
    )
    (net (code "58") (name "OF_NCS_3V") (class "Default")
      (node (ref "LS_OF") (pin "7") (pinfunction "A6_7") (pintype "bidirectional"))
    )
    (net (code "59") (name "OF_NPD") (class "Default")
      (node (ref "JST_OPTICAL-FLOW") (pin "5") (pinfunction "5_5") (pintype "bidirectional"))
      (node (ref "LS_OF") (pin "20") (pinfunction "B1_20") (pintype "bidirectional"))
    )
    (net (code "60") (name "OF_NPD_3V") (class "Default")
      (node (ref "LS_OF") (pin "1") (pinfunction "A1_1") (pintype "bidirectional"))
    )
    (net (code "61") (name "OF_RST") (class "Default")
      (node (ref "JST_OPTICAL-FLOW") (pin "7") (pinfunction "7_7") (pintype "bidirectional"))
      (node (ref "LS_OF") (pin "18") (pinfunction "B2_18") (pintype "bidirectional"))
    )
    (net (code "62") (name "OF_RST_3V") (class "Default")
      (node (ref "LS_OF") (pin "3") (pinfunction "A2_3") (pintype "bidirectional"))
    )
    (net (code "63") (name "POTI_ADC_1.8V") (class "Default")
      (node (ref "P9") (pin "39") (pinfunction "39_39") (pintype "passive"))
      (node (ref "RN5") (pin "1") (pinfunction "1_1") (pintype "passive"))
      (node (ref "RN6") (pin "8") (pinfunction "2_8") (pintype "passive"))
    )
    (net (code "64") (name "PWM0A") (class "Default")
      (node (ref "P9") (pin "22") (pinfunction "22_22") (pintype "passive"))
    )
    (net (code "65") (name "PWM0B") (class "Default")
      (node (ref "P9") (pin "21") (pinfunction "21_21") (pintype "passive"))
    )
    (net (code "66") (name "PWM1A") (class "Default")
      (node (ref "LS_OF") (pin "8") (pinfunction "A7_8") (pintype "bidirectional"))
      (node (ref "P9") (pin "14") (pinfunction "14_14") (pintype "passive"))
    )
    (net (code "67") (name "PWM1B") (class "Default")
      (node (ref "LS_OF") (pin "9") (pinfunction "A8_9") (pintype "bidirectional"))
      (node (ref "P9") (pin "16") (pinfunction "16_16") (pintype "passive"))
    )
    (net (code "68") (name "P_EOC") (class "Default")
      (node (ref "9AXIS-IMU") (pin "10") (pinfunction "10_10") (pintype "passive"))
      (node (ref "P8") (pin "46") (pinfunction "46_46") (pintype "passive"))
    )
    (net (code "69") (name "P_XCLR") (class "Default")
      (node (ref "9AXIS-IMU") (pin "9") (pinfunction "9_9") (pintype "passive"))
    )
    (net (code "70") (name "SERVO_PWM") (class "Default")
      (node (ref "JST_SERVO") (pin "3") (pinfunction "3_3") (pintype "bidirectional"))
      (node (ref "LS_OF") (pin "13") (pinfunction "B7_13") (pintype "bidirectional"))
    )
    (net (code "71") (name "SERVO_PWM2") (class "Default")
      (node (ref "JST_SERVO2") (pin "3") (pinfunction "3_3") (pintype "bidirectional"))
      (node (ref "LS_OF") (pin "12") (pinfunction "B8_12") (pintype "bidirectional"))
    )
    (net (code "72") (name "SPI1_CLK") (class "Default")
      (node (ref "LS_OF") (pin "4") (pinfunction "A3_4") (pintype "bidirectional"))
      (node (ref "P9") (pin "31") (pinfunction "31_31") (pintype "passive"))
    )
    (net (code "73") (name "SPI1_D0_MISO") (class "Default")
      (node (ref "LS_OF") (pin "5") (pinfunction "A4_5") (pintype "bidirectional"))
      (node (ref "P9") (pin "29") (pinfunction "29_29") (pintype "passive"))
    )
    (net (code "74") (name "SPI1_D1_MOSI") (class "Default")
      (node (ref "LS_OF") (pin "6") (pinfunction "A5_6") (pintype "bidirectional"))
      (node (ref "P9") (pin "30") (pinfunction "30_30") (pintype "passive"))
    )
    (net (code "75") (name "SPI_CLK") (class "Default")
      (node (ref "JST_OPTICAL-FLOW") (pin "6") (pinfunction "6_6") (pintype "bidirectional"))
      (node (ref "LS_OF") (pin "17") (pinfunction "B3_17") (pintype "bidirectional"))
    )
    (net (code "76") (name "SPI_MISO") (class "Default")
      (node (ref "JST_OPTICAL-FLOW") (pin "4") (pinfunction "4_4") (pintype "bidirectional"))
      (node (ref "LS_OF") (pin "16") (pinfunction "B4_16") (pintype "bidirectional"))
    )
    (net (code "77") (name "SPI_MOSI") (class "Default")
      (node (ref "JST_OPTICAL-FLOW") (pin "2") (pinfunction "2_2") (pintype "bidirectional"))
      (node (ref "LS_OF") (pin "15") (pinfunction "B5_15") (pintype "bidirectional"))
    )
    (net (code "78") (name "SW_BUNDLE") (class "Default")
      (node (ref "RN3") (pin "7") (pinfunction "2_7") (pintype "passive"))
      (node (ref "STECKER_BOX") (pin "7") (pinfunction "7_7") (pintype "passive"))
    )
    (net (code "79") (name "SW_BUNDLE-LED") (class "Default")
      (node (ref "PNP2") (pin "C") (pinfunction "C_C") (pintype "passive"))
      (node (ref "STECKER_BOX") (pin "8") (pinfunction "8_8") (pintype "passive"))
    )
    (net (code "80") (name "SW_BUNDLE-LED_3V") (class "Default")
      (node (ref "NPN2") (pin "B") (pinfunction "B_B") (pintype "passive"))
      (node (ref "RN2") (pin "7") (pinfunction "2_7") (pintype "passive"))
    )
    (net (code "81") (name "SW_BUNDLE_3V") (class "Default")
      (node (ref "P9") (pin "13") (pinfunction "13_13") (pintype "passive"))
      (node (ref "RN3") (pin "2") (pinfunction "1_2") (pintype "passive"))
      (node (ref "RN4") (pin "6") (pinfunction "2_6") (pintype "passive"))
    )
    (net (code "82") (name "SW_PWR_BUT") (class "Default")
      (node (ref "P9") (pin "9") (pinfunction "9_9") (pintype "passive"))
      (node (ref "STECKER_BOX") (pin "9") (pinfunction "9_9") (pintype "passive"))
    )
    (net (code "83") (name "SW_UNUSED") (class "Default")
      (node (ref "RN3") (pin "6") (pinfunction "2_6") (pintype "passive"))
    )
    (net (code "84") (name "SW_UNUSED-LED") (class "Default")
      (node (ref "PNP3") (pin "C") (pinfunction "C_C") (pintype "passive"))
      (node (ref "STECKER_BOX") (pin "10") (pinfunction "10_10") (pintype "passive"))
    )
    (net (code "85") (name "SW_UNUSED-LED_3V") (class "Default")
      (node (ref "NPN3") (pin "B") (pinfunction "B_B") (pintype "passive"))
      (node (ref "RN2") (pin "8") (pinfunction "2_8") (pintype "passive"))
    )
    (net (code "86") (name "SW_UNUSED_3V") (class "Default")
      (node (ref "P9") (pin "12") (pinfunction "12_12") (pintype "passive"))
      (node (ref "RN3") (pin "3") (pinfunction "1_3") (pintype "passive"))
      (node (ref "RN4") (pin "7") (pinfunction "2_7") (pintype "passive"))
    )
    (net (code "87") (name "SW_VISION") (class "Default")
      (node (ref "RN3") (pin "8") (pinfunction "2_8") (pintype "passive"))
      (node (ref "STECKER_BOX") (pin "5") (pinfunction "5_5") (pintype "passive"))
    )
    (net (code "88") (name "SW_VISION-LED") (class "Default")
      (node (ref "PNP1") (pin "C") (pinfunction "C_C") (pintype "passive"))
      (node (ref "STECKER_BOX") (pin "6") (pinfunction "6_6") (pintype "passive"))
    )
    (net (code "89") (name "SW_VISION-LED_3V") (class "Default")
      (node (ref "NPN1") (pin "B") (pinfunction "B_B") (pintype "passive"))
      (node (ref "RN2") (pin "6") (pinfunction "2_6") (pintype "passive"))
    )
    (net (code "90") (name "SW_VISION_3V") (class "Default")
      (node (ref "P9") (pin "11") (pinfunction "11_11") (pintype "passive"))
      (node (ref "RN3") (pin "1") (pinfunction "1_1") (pintype "passive"))
      (node (ref "RN4") (pin "8") (pinfunction "2_8") (pintype "passive"))
    )
    (net (code "91") (name "T_INT1") (class "Default")
      (node (ref "9AXIS-IMU") (pin "8") (pinfunction "8_8") (pintype "passive"))
      (node (ref "P8") (pin "45") (pinfunction "45_45") (pintype "passive"))
    )
    (net (code "92") (name "VADC") (class "Default")
      (node (ref "P9") (pin "32") (pinfunction "32_32") (pintype "passive"))
    )
    (net (code "93") (name "unconnected-(9AXIS-IMU-Pad1)") (class "Default")
      (node (ref "9AXIS-IMU") (pin "1") (pinfunction "1_1") (pintype "passive"))
    )
    (net (code "94") (name "unconnected-(BALL-HANDLE_LEFT-Pad7)") (class "Default")
      (node (ref "BALL-HANDLE_LEFT") (pin "7") (pinfunction "7_7") (pintype "passive"))
    )
    (net (code "95") (name "unconnected-(BALL-HANDLE_LEFT-Pad8)") (class "Default")
      (node (ref "BALL-HANDLE_LEFT") (pin "8") (pinfunction "8_8") (pintype "passive"))
    )
    (net (code "96") (name "unconnected-(BALL-HANDLE_RIGHT-Pad7)") (class "Default")
      (node (ref "BALL-HANDLE_RIGHT") (pin "7") (pinfunction "7_7") (pintype "passive"))
    )
    (net (code "97") (name "unconnected-(BALL-HANDLE_RIGHT-Pad8)") (class "Default")
      (node (ref "BALL-HANDLE_RIGHT") (pin "8") (pinfunction "8_8") (pintype "passive"))
    )
    (net (code "98") (name "unconnected-(LS_BH_L-A1-Pad1)") (class "Default")
      (node (ref "LS_BH_L") (pin "1") (pinfunction "A1_1") (pintype "bidirectional"))
    )
    (net (code "99") (name "unconnected-(LS_BH_L-A2-Pad3)") (class "Default")
      (node (ref "LS_BH_L") (pin "3") (pinfunction "A2_3") (pintype "bidirectional"))
    )
    (net (code "100") (name "unconnected-(LS_BH_L-A3-Pad4)") (class "Default")
      (node (ref "LS_BH_L") (pin "4") (pinfunction "A3_4") (pintype "bidirectional"))
    )
    (net (code "101") (name "unconnected-(LS_BH_L-B1-Pad20)") (class "Default")
      (node (ref "LS_BH_L") (pin "20") (pinfunction "B1_20") (pintype "bidirectional"))
    )
    (net (code "102") (name "unconnected-(LS_BH_L-B2-Pad18)") (class "Default")
      (node (ref "LS_BH_L") (pin "18") (pinfunction "B2_18") (pintype "bidirectional"))
    )
    (net (code "103") (name "unconnected-(LS_BH_L-B3-Pad17)") (class "Default")
      (node (ref "LS_BH_L") (pin "17") (pinfunction "B3_17") (pintype "bidirectional"))
    )
    (net (code "104") (name "unconnected-(LS_BH_R-A8-Pad9)") (class "Default")
      (node (ref "LS_BH_R") (pin "9") (pinfunction "A8_9") (pintype "bidirectional"))
    )
    (net (code "105") (name "unconnected-(LS_BH_R-B8-Pad12)") (class "Default")
      (node (ref "LS_BH_R") (pin "12") (pinfunction "B8_12") (pintype "bidirectional"))
    )
    (net (code "106") (name "unconnected-(P8-Pad3)") (class "Default")
      (node (ref "P8") (pin "3") (pinfunction "3_3") (pintype "passive"))
    )
    (net (code "107") (name "unconnected-(P8-Pad4)") (class "Default")
      (node (ref "P8") (pin "4") (pinfunction "4_4") (pintype "passive"))
    )
    (net (code "108") (name "unconnected-(P8-Pad5)") (class "Default")
      (node (ref "P8") (pin "5") (pinfunction "5_5") (pintype "passive"))
    )
    (net (code "109") (name "unconnected-(P8-Pad6)") (class "Default")
      (node (ref "P8") (pin "6") (pinfunction "6_6") (pintype "passive"))
    )
    (net (code "110") (name "unconnected-(P8-Pad7)") (class "Default")
      (node (ref "P8") (pin "7") (pinfunction "7_7") (pintype "passive"))
    )
    (net (code "111") (name "unconnected-(P8-Pad8)") (class "Default")
      (node (ref "P8") (pin "8") (pinfunction "8_8") (pintype "passive"))
    )
    (net (code "112") (name "unconnected-(P8-Pad9)") (class "Default")
      (node (ref "P8") (pin "9") (pinfunction "9_9") (pintype "passive"))
    )
    (net (code "113") (name "unconnected-(P8-Pad10)") (class "Default")
      (node (ref "P8") (pin "10") (pinfunction "10_10") (pintype "passive"))
    )
    (net (code "114") (name "unconnected-(P8-Pad11)") (class "Default")
      (node (ref "P8") (pin "11") (pinfunction "11_11") (pintype "passive"))
    )
    (net (code "115") (name "unconnected-(P8-Pad12)") (class "Default")
      (node (ref "P8") (pin "12") (pinfunction "12_12") (pintype "passive"))
    )
    (net (code "116") (name "unconnected-(P8-Pad14)") (class "Default")
      (node (ref "P8") (pin "14") (pinfunction "14_14") (pintype "passive"))
    )
    (net (code "117") (name "unconnected-(P8-Pad15)") (class "Default")
      (node (ref "P8") (pin "15") (pinfunction "15_15") (pintype "passive"))
    )
    (net (code "118") (name "unconnected-(P8-Pad16)") (class "Default")
      (node (ref "P8") (pin "16") (pinfunction "16_16") (pintype "passive"))
    )
    (net (code "119") (name "unconnected-(P8-Pad17)") (class "Default")
      (node (ref "P8") (pin "17") (pinfunction "17_17") (pintype "passive"))
    )
    (net (code "120") (name "unconnected-(P8-Pad18)") (class "Default")
      (node (ref "P8") (pin "18") (pinfunction "18_18") (pintype "passive"))
    )
    (net (code "121") (name "unconnected-(P8-Pad20)") (class "Default")
      (node (ref "P8") (pin "20") (pinfunction "20_20") (pintype "passive"))
    )
    (net (code "122") (name "unconnected-(P8-Pad21)") (class "Default")
      (node (ref "P8") (pin "21") (pinfunction "21_21") (pintype "passive"))
    )
    (net (code "123") (name "unconnected-(P8-Pad22)") (class "Default")
      (node (ref "P8") (pin "22") (pinfunction "22_22") (pintype "passive"))
    )
    (net (code "124") (name "unconnected-(P8-Pad23)") (class "Default")
      (node (ref "P8") (pin "23") (pinfunction "23_23") (pintype "passive"))
    )
    (net (code "125") (name "unconnected-(P8-Pad24)") (class "Default")
      (node (ref "P8") (pin "24") (pinfunction "24_24") (pintype "passive"))
    )
    (net (code "126") (name "unconnected-(P8-Pad25)") (class "Default")
      (node (ref "P8") (pin "25") (pinfunction "25_25") (pintype "passive"))
    )
    (net (code "127") (name "unconnected-(P8-Pad26)") (class "Default")
      (node (ref "P8") (pin "26") (pinfunction "26_26") (pintype "passive"))
    )
    (net (code "128") (name "unconnected-(P8-Pad27)") (class "Default")
      (node (ref "P8") (pin "27") (pinfunction "27_27") (pintype "passive"))
    )
    (net (code "129") (name "unconnected-(P8-Pad28)") (class "Default")
      (node (ref "P8") (pin "28") (pinfunction "28_28") (pintype "passive"))
    )
    (net (code "130") (name "unconnected-(P8-Pad29)") (class "Default")
      (node (ref "P8") (pin "29") (pinfunction "29_29") (pintype "passive"))
    )
    (net (code "131") (name "unconnected-(P8-Pad30)") (class "Default")
      (node (ref "P8") (pin "30") (pinfunction "30_30") (pintype "passive"))
    )
    (net (code "132") (name "unconnected-(P8-Pad31)") (class "Default")
      (node (ref "P8") (pin "31") (pinfunction "31_31") (pintype "passive"))
    )
    (net (code "133") (name "unconnected-(P8-Pad32)") (class "Default")
      (node (ref "P8") (pin "32") (pinfunction "32_32") (pintype "passive"))
    )
    (net (code "134") (name "unconnected-(P8-Pad33)") (class "Default")
      (node (ref "P8") (pin "33") (pinfunction "33_33") (pintype "passive"))
    )
    (net (code "135") (name "unconnected-(P8-Pad35)") (class "Default")
      (node (ref "P8") (pin "35") (pinfunction "35_35") (pintype "passive"))
    )
    (net (code "136") (name "unconnected-(P9-Pad7)") (class "Default")
      (node (ref "P9") (pin "7") (pinfunction "7_7") (pintype "passive"))
    )
    (net (code "137") (name "unconnected-(P9-Pad8)") (class "Default")
      (node (ref "P9") (pin "8") (pinfunction "8_8") (pintype "passive"))
    )
    (net (code "138") (name "unconnected-(P9-Pad15)") (class "Default")
      (node (ref "P9") (pin "15") (pinfunction "15_15") (pintype "passive"))
    )
    (net (code "139") (name "unconnected-(P9-Pad23)") (class "Default")
      (node (ref "P9") (pin "23") (pinfunction "23_23") (pintype "passive"))
    )
    (net (code "140") (name "unconnected-(P9-Pad24)") (class "Default")
      (node (ref "P9") (pin "24") (pinfunction "24_24") (pintype "passive"))
    )
    (net (code "141") (name "unconnected-(P9-Pad25)") (class "Default")
      (node (ref "P9") (pin "25") (pinfunction "25_25") (pintype "passive"))
    )
    (net (code "142") (name "unconnected-(P9-Pad26)") (class "Default")
      (node (ref "P9") (pin "26") (pinfunction "26_26") (pintype "passive"))
    )
    (net (code "143") (name "unconnected-(P9-Pad27)") (class "Default")
      (node (ref "P9") (pin "27") (pinfunction "27_27") (pintype "passive"))
    )
    (net (code "144") (name "unconnected-(P9-Pad28)") (class "Default")
      (node (ref "P9") (pin "28") (pinfunction "28_28") (pintype "passive"))
    )
    (net (code "145") (name "unconnected-(P9-Pad41)") (class "Default")
      (node (ref "P9") (pin "41") (pinfunction "41_41") (pintype "passive"))
    )
    (net (code "146") (name "unconnected-(P9-Pad42)") (class "Default")
      (node (ref "P9") (pin "42") (pinfunction "42_42") (pintype "passive"))
    )
    (net (code "147") (name "unconnected-(RN1D-1-Pad4)") (class "Default")
      (node (ref "RN1") (pin "4") (pinfunction "1_4") (pintype "passive"))
    )
    (net (code "148") (name "unconnected-(RN2D-2-Pad5)") (class "Default")
      (node (ref "RN2") (pin "5") (pinfunction "2_5") (pintype "passive"))
    )
    (net (code "149") (name "unconnected-(RN3D-1-Pad4)") (class "Default")
      (node (ref "RN3") (pin "4") (pinfunction "1_4") (pintype "passive"))
    )
    (net (code "150") (name "unconnected-(RN3D-2-Pad5)") (class "Default")
      (node (ref "RN3") (pin "5") (pinfunction "2_5") (pintype "passive"))
    )
    (net (code "151") (name "unconnected-(RN4D-2-Pad5)") (class "Default")
      (node (ref "RN4") (pin "5") (pinfunction "2_5") (pintype "passive"))
    )
    (net (code "152") (name "unconnected-(RN7C-1-Pad3)") (class "Default")
      (node (ref "RN7") (pin "3") (pinfunction "1_3") (pintype "passive"))
    )
    (net (code "153") (name "unconnected-(RN7C-2-Pad6)") (class "Default")
      (node (ref "RN7") (pin "6") (pinfunction "2_6") (pintype "passive"))
    )
    (net (code "154") (name "unconnected-(RN7D-1-Pad4)") (class "Default")
      (node (ref "RN7") (pin "4") (pinfunction "1_4") (pintype "passive"))
    )
    (net (code "155") (name "unconnected-(RN7D-2-Pad5)") (class "Default")
      (node (ref "RN7") (pin "5") (pinfunction "2_5") (pintype "passive"))
    )
    (net (code "156") (name "unconnected-(RN8C-1-Pad3)") (class "Default")
      (node (ref "RN8") (pin "3") (pinfunction "1_3") (pintype "passive"))
    )
    (net (code "157") (name "unconnected-(RN8C-2-Pad6)") (class "Default")
      (node (ref "RN8") (pin "6") (pinfunction "2_6") (pintype "passive"))
    )
    (net (code "158") (name "unconnected-(RN8D-1-Pad4)") (class "Default")
      (node (ref "RN8") (pin "4") (pinfunction "1_4") (pintype "passive"))
    )
    (net (code "159") (name "unconnected-(RN8D-2-Pad5)") (class "Default")
      (node (ref "RN8") (pin "5") (pinfunction "2_5") (pintype "passive"))
    )
    (net (code "160") (name "unconnected-(STECKER_BOX-Pad3)") (class "Default")
      (node (ref "STECKER_BOX") (pin "3") (pinfunction "3_3") (pintype "passive"))
    )
    (net (code "161") (name "unconnected-(STECKER_BOX-Pad4)") (class "Default")
      (node (ref "STECKER_BOX") (pin "4") (pinfunction "4_4") (pintype "passive"))
    )
    (net (code "162") (name "unconnected-(U$1-VREF-Pad5)") (class "Default")
      (node (ref "U$1") (pin "5") (pinfunction "VREF_5") (pintype "output"))
    )
    (net (code "163") (name "~{BH_L_RESET_3V}") (class "Default")
      (node (ref "LS_BH_L") (pin "7") (pinfunction "A6_7") (pintype "bidirectional"))
      (node (ref "P8") (pin "39") (pinfunction "39_39") (pintype "passive"))
    )
    (net (code "164") (name "~{BH_L_RESET}") (class "Default")
      (node (ref "BALL-HANDLE_LEFT") (pin "4") (pinfunction "4_4") (pintype "passive"))
      (node (ref "LS_BH_L") (pin "14") (pinfunction "B6_14") (pintype "bidirectional"))
    )
    (net (code "165") (name "~{BH_R_RESET_3V}") (class "Default")
      (node (ref "LS_BH_R") (pin "4") (pinfunction "A3_4") (pintype "bidirectional"))
      (node (ref "P8") (pin "34") (pinfunction "34_34") (pintype "passive"))
    )
    (net (code "166") (name "~{BH_R_RESET}") (class "Default")
      (node (ref "BALL-HANDLE_RIGHT") (pin "4") (pinfunction "4_4") (pintype "passive"))
      (node (ref "LS_BH_R") (pin "17") (pinfunction "B3_17") (pintype "bidirectional"))
    )
    (net (code "167") (name "~{SYS_RESET}") (class "Default")
      (node (ref "P9") (pin "10") (pinfunction "10_10") (pintype "passive"))
    )
  )
)
